# Inflow_slave.net
KiCad netlist of a schematic drawn in EAGLE
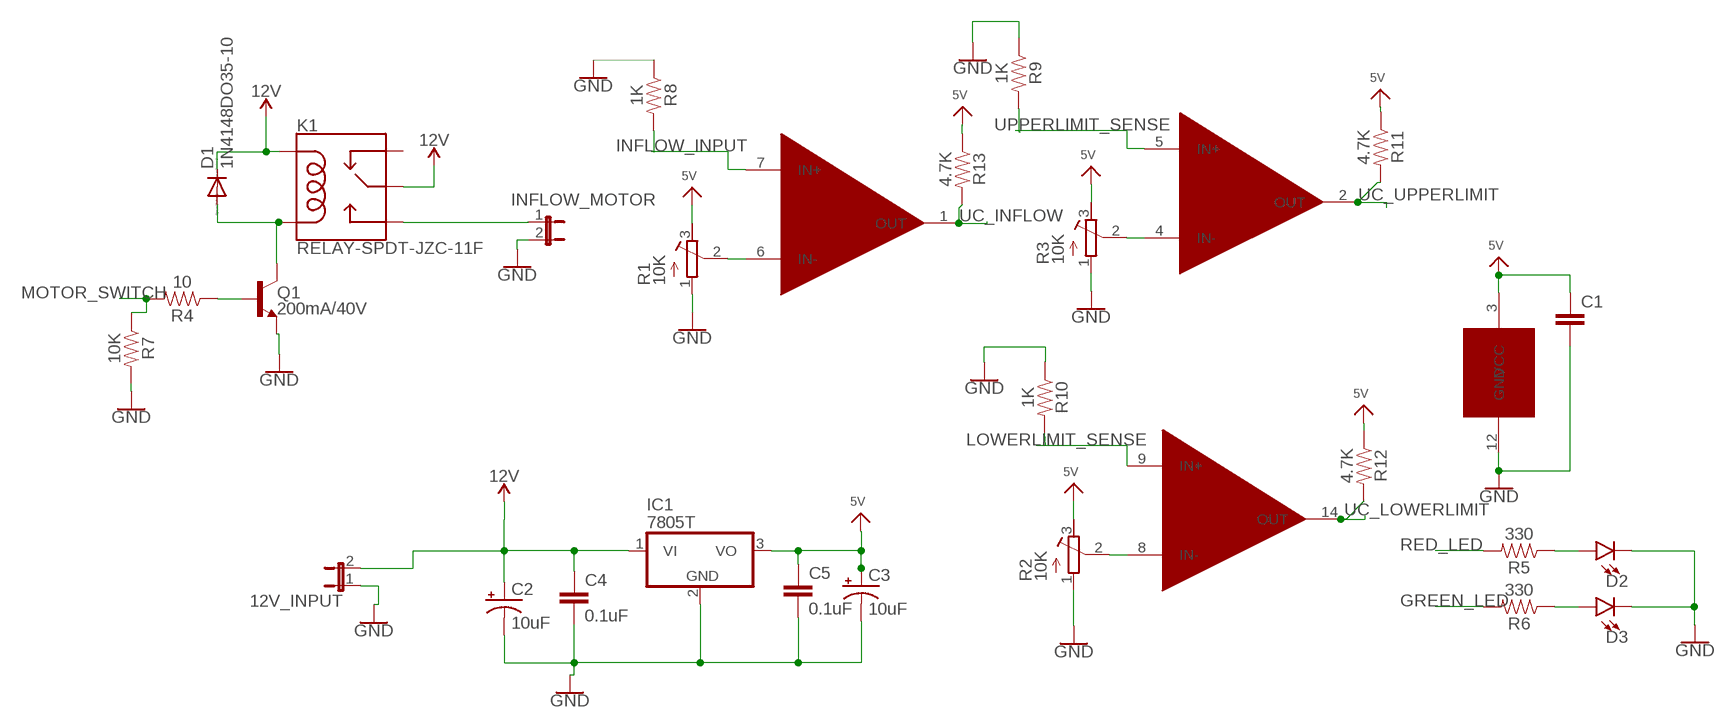
[diagram p0: schematic, sheet 1]

(export (version "E")
  (design (tool "Eeschema 10.0.6"))
  (components
    (comp (ref "12V_INPUT")
      (value "JUMPER-2PTH")
      (footprint "eagle-import:1X02")
      (libsource (lib "eagle-import") (part "JUMPER-2PTH"))
    )
    (comp (ref "C1")
      (value "C-EUC0805K")
      (footprint "eagle-import:C0805K")
      (libsource (lib "eagle-import") (part "C-EUC0805K"))
    )
    (comp (ref "C2")
      (value "10uF")
      (footprint "eagle-import:CPOL-RADIAL-2.5MM-5MM")
      (libsource (lib "eagle-import") (part "10UF-POLAR-RADIAL-2.5MM-25V-20%"))
    )
    (comp (ref "C3")
      (value "10uF")
      (footprint "eagle-import:CPOL-RADIAL-2.5MM-5MM")
      (libsource (lib "eagle-import") (part "10UF-POLAR-RADIAL-2.5MM-25V-20%"))
    )
    (comp (ref "C4")
      (value "0.1uF")
      (footprint "eagle-import:CAP-PTH-SMALL-KIT")
      (libsource (lib "eagle-import") (part "0.1UF-KIT-EZ-50V-20%"))
    )
    (comp (ref "C5")
      (value "0.1uF")
      (footprint "eagle-import:CAP-PTH-SMALL-KIT")
      (libsource (lib "eagle-import") (part "0.1UF-KIT-EZ-50V-20%"))
    )
    (comp (ref "D1")
      (value "1N4148DO35-10")
      (footprint "eagle-import:DO35-10")
      (libsource (lib "eagle-import") (part "1N4148DO35-10"))
    )
    (comp (ref "D2")
      (value "LED5MM")
      (footprint "eagle-import:LED_5MM")
      (libsource (lib "eagle-import") (part "LED5MM"))
    )
    (comp (ref "D3")
      (value "LED5MM")
      (footprint "eagle-import:LED_5MM")
      (libsource (lib "eagle-import") (part "LED5MM"))
    )
    (comp (ref "IC1")
      (value "7805T")
      (footprint "eagle-import:TO220H")
      (libsource (lib "eagle-import") (part "78T05"))
    )
    (comp (ref "INFLOW_MOTOR")
      (value "JUMPER-2PTH")
      (footprint "eagle-import:1X02")
      (libsource (lib "eagle-import") (part "JUMPER-2PTH"))
    )
    (comp (ref "K1")
      (value "RELAY-SPDT-JZC-11F")
      (footprint "eagle-import:RELAY-JZC")
      (libsource (lib "eagle-import") (part "RELAY-SPDT-JZC-11F"))
    )
    (comp (ref "Q1")
      (value "200mA/40V")
      (footprint "eagle-import:TO-92")
      (libsource (lib "eagle-import") (part "TRANS_NPN-2N3904"))
    )
    (comp (ref "R1")
      (value "10K")
      (footprint "eagle-import:RTRIM64W")
      (libsource (lib "eagle-import") (part "R-TRIMM64W"))
    )
    (comp (ref "R2")
      (value "10K")
      (footprint "eagle-import:RTRIM64W")
      (libsource (lib "eagle-import") (part "R-TRIMM64W"))
    )
    (comp (ref "R3")
      (value "10K")
      (footprint "eagle-import:RTRIM64W")
      (libsource (lib "eagle-import") (part "R-TRIMM64W"))
    )
    (comp (ref "R4")
      (value "10")
      (footprint "eagle-import:AXIAL-0.3")
      (libsource (lib "eagle-import") (part "10OHM-HORIZ-1/4W-1%"))
    )
    (comp (ref "R5")
      (value "330")
      (footprint "eagle-import:AXIAL-0.3")
      (libsource (lib "eagle-import") (part "330OHM-HORIZ-1/10W-5%"))
    )
    (comp (ref "R6")
      (value "330")
      (footprint "eagle-import:AXIAL-0.3")
      (libsource (lib "eagle-import") (part "330OHM-HORIZ-1/10W-5%"))
    )
    (comp (ref "R7")
      (value "10K")
      (footprint "eagle-import:AXIAL-0.3")
      (libsource (lib "eagle-import") (part "10OHM-HORIZ-1/4W-1%"))
    )
    (comp (ref "R8")
      (value "1K")
      (footprint "eagle-import:AXIAL-0.3")
      (libsource (lib "eagle-import") (part "330OHM-HORIZ-1/10W-5%"))
    )
    (comp (ref "R9")
      (value "1K")
      (footprint "eagle-import:AXIAL-0.3")
      (libsource (lib "eagle-import") (part "330OHM-HORIZ-1/10W-5%"))
    )
    (comp (ref "R10")
      (value "1K")
      (footprint "eagle-import:AXIAL-0.3")
      (libsource (lib "eagle-import") (part "330OHM-HORIZ-1/10W-5%"))
    )
    (comp (ref "R11")
      (value "4.7K")
      (footprint "eagle-import:AXIAL-0.3")
      (libsource (lib "eagle-import") (part "330OHM-HORIZ-1/10W-5%"))
    )
    (comp (ref "R12")
      (value "4.7K")
      (footprint "eagle-import:AXIAL-0.3")
      (libsource (lib "eagle-import") (part "330OHM-HORIZ-1/10W-5%"))
    )
    (comp (ref "R13")
      (value "4.7K")
      (footprint "eagle-import:AXIAL-0.3")
      (libsource (lib "eagle-import") (part "330OHM-HORIZ-1/10W-5%"))
    )
    (comp (ref "U$1")
      (value "LM339_DEV")
      (footprint "eagle-import:DIP14")
      (libsource (lib "eagle-import") (part "LM339_DEV"))
    )
  )
  (nets
    (net (code "1") (name "/GREEN_LED") (class "Default")
      (node (ref "R6") (pin "P$2") (pinfunction "2_P$2") (pintype "passive"))
    )
    (net (code "2") (name "/INFLOW_INPUT") (class "Default")
      (node (ref "R8") (pin "P$2") (pinfunction "2_P$2") (pintype "passive"))
      (node (ref "U$1") (pin "7") (pinfunction "IN+_7") (pintype "bidirectional"))
    )
    (net (code "3") (name "/LOWERLIMIT_SENSE") (class "Default")
      (node (ref "R10") (pin "P$2") (pinfunction "2_P$2") (pintype "passive"))
      (node (ref "U$1") (pin "9") (pinfunction "IN+_9") (pintype "bidirectional"))
    )
    (net (code "4") (name "/MOTOR_SWITCH") (class "Default")
      (node (ref "R4") (pin "P$2") (pinfunction "2_P$2") (pintype "passive"))
      (node (ref "R7") (pin "P$1") (pinfunction "1_P$1") (pintype "passive"))
    )
    (net (code "5") (name "/RED_LED") (class "Default")
      (node (ref "R5") (pin "P$2") (pinfunction "2_P$2") (pintype "passive"))
    )
    (net (code "6") (name "/UC_INFLOW") (class "Default")
      (node (ref "R13") (pin "P$2") (pinfunction "2_P$2") (pintype "passive"))
      (node (ref "U$1") (pin "1") (pinfunction "OUT_1") (pintype "bidirectional"))
    )
    (net (code "7") (name "/UC_LOWERLIMIT") (class "Default")
      (node (ref "R12") (pin "P$2") (pinfunction "2_P$2") (pintype "passive"))
      (node (ref "U$1") (pin "14") (pinfunction "OUT_14") (pintype "bidirectional"))
    )
    (net (code "8") (name "/UC_UPPERLIMIT") (class "Default")
      (node (ref "R11") (pin "P$2") (pinfunction "2_P$2") (pintype "passive"))
      (node (ref "U$1") (pin "2") (pinfunction "OUT_2") (pintype "bidirectional"))
    )
    (net (code "9") (name "/UPPERLIMIT_SENSE") (class "Default")
      (node (ref "R9") (pin "P$2") (pinfunction "2_P$2") (pintype "passive"))
      (node (ref "U$1") (pin "5") (pinfunction "IN+_5") (pintype "bidirectional"))
    )
    (net (code "10") (name "5V") (class "Default")
      (node (ref "C1") (pin "1") (pinfunction "1_1") (pintype "passive"))
      (node (ref "C3") (pin "1") (pinfunction "+_1") (pintype "passive"))
      (node (ref "C5") (pin "1") (pinfunction "1_1") (pintype "passive"))
      (node (ref "IC1") (pin "3") (pinfunction "VO_3") (pintype "passive"))
      (node (ref "R1") (pin "3") (pinfunction "E_3") (pintype "passive"))
      (node (ref "R11") (pin "P$1") (pinfunction "1_P$1") (pintype "passive"))
      (node (ref "R12") (pin "P$1") (pinfunction "1_P$1") (pintype "passive"))
      (node (ref "R13") (pin "P$1") (pinfunction "1_P$1") (pintype "passive"))
      (node (ref "R2") (pin "3") (pinfunction "E_3") (pintype "passive"))
      (node (ref "R3") (pin "3") (pinfunction "E_3") (pintype "passive"))
      (node (ref "U$1") (pin "3") (pinfunction "VCC_3") (pintype "bidirectional"))
    )
    (net (code "11") (name "12V") (class "Default")
      (node (ref "12V_INPUT") (pin "2") (pinfunction "2_2") (pintype "passive"))
      (node (ref "C2") (pin "1") (pinfunction "+_1") (pintype "passive"))
      (node (ref "C4") (pin "1") (pinfunction "1_1") (pintype "passive"))
      (node (ref "D1") (pin "C") (pinfunction "C_C") (pintype "passive"))
      (node (ref "IC1") (pin "1") (pinfunction "VI_1") (pintype "input"))
      (node (ref "K1") (pin "4") (pinfunction "MAIN_4") (pintype "bidirectional"))
      (node (ref "K1") (pin "5") (pinfunction "COIL1_5") (pintype "bidirectional"))
    )
    (net (code "12") (name "GND") (class "Default")
      (node (ref "12V_INPUT") (pin "1") (pinfunction "1_1") (pintype "passive"))
      (node (ref "C1") (pin "2") (pinfunction "2_2") (pintype "passive"))
      (node (ref "C2") (pin "2") (pinfunction "-_2") (pintype "passive"))
      (node (ref "C3") (pin "2") (pinfunction "-_2") (pintype "passive"))
      (node (ref "C4") (pin "2") (pinfunction "2_2") (pintype "passive"))
      (node (ref "C5") (pin "2") (pinfunction "2_2") (pintype "passive"))
      (node (ref "D2") (pin "K") (pinfunction "C_K") (pintype "passive"))
      (node (ref "D3") (pin "K") (pinfunction "C_K") (pintype "passive"))
      (node (ref "IC1") (pin "2") (pinfunction "GND_2") (pintype "passive"))
      (node (ref "INFLOW_MOTOR") (pin "2") (pinfunction "2_2") (pintype "passive"))
      (node (ref "Q1") (pin "1") (pinfunction "E_1") (pintype "passive"))
      (node (ref "R1") (pin "1") (pinfunction "A_1") (pintype "passive"))
      (node (ref "R10") (pin "P$1") (pinfunction "1_P$1") (pintype "passive"))
      (node (ref "R2") (pin "1") (pinfunction "A_1") (pintype "passive"))
      (node (ref "R3") (pin "1") (pinfunction "A_1") (pintype "passive"))
      (node (ref "R7") (pin "P$2") (pinfunction "2_P$2") (pintype "passive"))
      (node (ref "R8") (pin "P$1") (pinfunction "1_P$1") (pintype "passive"))
      (node (ref "R9") (pin "P$1") (pinfunction "1_P$1") (pintype "passive"))
      (node (ref "U$1") (pin "12") (pinfunction "GND_12") (pintype "bidirectional"))
    )
    (net (code "13") (name "Net-(K1-COIL2)") (class "Default")
      (node (ref "D1") (pin "A") (pinfunction "A_A") (pintype "passive"))
      (node (ref "K1") (pin "1") (pinfunction "COIL2_1") (pintype "bidirectional"))
      (node (ref "Q1") (pin "3") (pinfunction "C_3") (pintype "passive"))
    )
    (net (code "14") (name "Net-(K1-NO)") (class "Default")
      (node (ref "INFLOW_MOTOR") (pin "1") (pinfunction "1_1") (pintype "passive"))
      (node (ref "K1") (pin "3") (pinfunction "NO_3") (pintype "bidirectional"))
    )
    (net (code "15") (name "Net-(Q1-B)") (class "Default")
      (node (ref "Q1") (pin "2") (pinfunction "B_2") (pintype "passive"))
      (node (ref "R4") (pin "P$1") (pinfunction "1_P$1") (pintype "passive"))
    )
    (net (code "16") (name "Net-(R1-S)") (class "Default")
      (node (ref "R1") (pin "2") (pinfunction "S_2") (pintype "passive"))
      (node (ref "U$1") (pin "6") (pinfunction "IN-_6") (pintype "bidirectional"))
    )
    (net (code "17") (name "Net-(R2-S)") (class "Default")
      (node (ref "R2") (pin "2") (pinfunction "S_2") (pintype "passive"))
      (node (ref "U$1") (pin "8") (pinfunction "IN-_8") (pintype "bidirectional"))
    )
    (net (code "18") (name "Net-(R3-S)") (class "Default")
      (node (ref "R3") (pin "2") (pinfunction "S_2") (pintype "passive"))
      (node (ref "U$1") (pin "4") (pinfunction "IN-_4") (pintype "bidirectional"))
    )
    (net (code "19") (name "Net-(R5-1)") (class "Default")
      (node (ref "D2") (pin "A") (pinfunction "A_A") (pintype "passive"))
      (node (ref "R5") (pin "P$1") (pinfunction "1_P$1") (pintype "passive"))
    )
    (net (code "20") (name "Net-(R6-1)") (class "Default")
      (node (ref "D3") (pin "A") (pinfunction "A_A") (pintype "passive"))
      (node (ref "R6") (pin "P$1") (pinfunction "1_P$1") (pintype "passive"))
    )
    (net (code "21") (name "unconnected-(K1-NC-Pad2)") (class "Default")
      (node (ref "K1") (pin "2") (pinfunction "NC_2") (pintype "bidirectional"))
    )
  )
)
